# LEOPADMINI.net
KiCad netlist of a schematic drawn in EAGLE
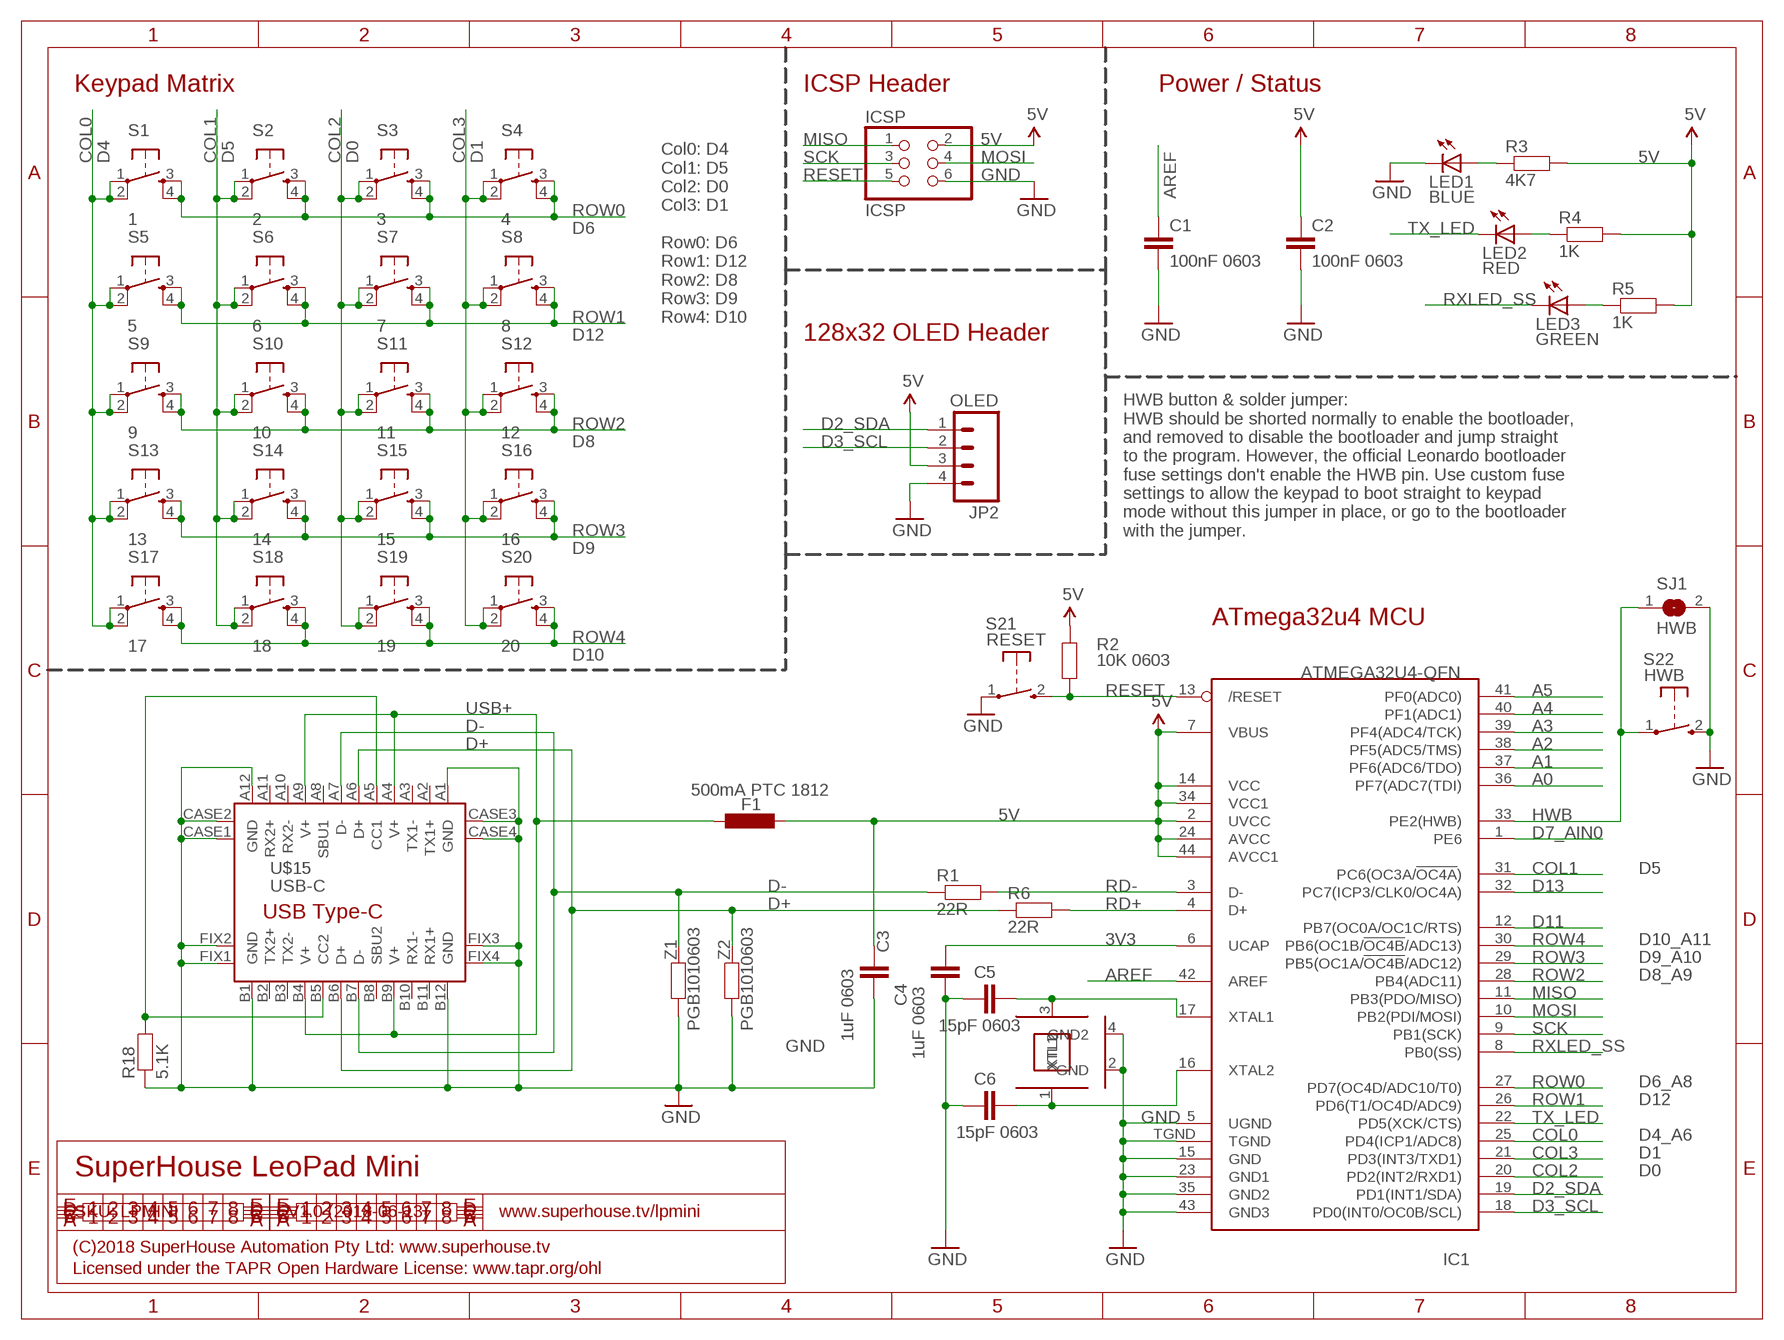
[diagram p0: schematic, sheet 1]

(export (version "E")
  (design (tool "Eeschema 10.0.6"))
  (components
    (comp (ref "C1")
      (value "100nF 0603")
      (footprint "eagle-import:0603")
      (libsource (lib "eagle-import") (part "CAP0603"))
    )
    (comp (ref "C2")
      (value "100nF 0603")
      (footprint "eagle-import:0603")
      (libsource (lib "eagle-import") (part "CAP0603"))
    )
    (comp (ref "C3")
      (value "1uF 0603")
      (footprint "eagle-import:0603")
      (libsource (lib "eagle-import") (part "CAP0603"))
    )
    (comp (ref "C4")
      (value "1uF 0603")
      (footprint "eagle-import:0603")
      (libsource (lib "eagle-import") (part "CAP0603"))
    )
    (comp (ref "C5")
      (value "15pF 0603")
      (footprint "eagle-import:0603")
      (libsource (lib "eagle-import") (part "CAP0603"))
    )
    (comp (ref "C6")
      (value "15pF 0603")
      (footprint "eagle-import:0603")
      (libsource (lib "eagle-import") (part "CAP0603"))
    )
    (comp (ref "F1")
      (value "500mA PTC 1812")
      (footprint "eagle-import:L1812")
      (libsource (lib "eagle-import") (part "L-EUL1812"))
    )
    (comp (ref "IC1")
      (value "ATMEGA32U4-QFN")
      (footprint "eagle-import:QFN-44N")
      (libsource (lib "eagle-import") (part "ATMEGA32U4-QFN"))
    )
    (comp (ref "ICSP")
      (value "ICSP")
      (footprint "eagle-import:2X03")
      (libsource (lib "eagle-import") (part "PINHD-2X3"))
    )
    (comp (ref "JP2")
      (value "OLED")
      (footprint "eagle-import:1X04")
      (libsource (lib "eagle-import") (part "M04PTH"))
    )
    (comp (ref "LED1")
      (value "BLUE")
      (footprint "eagle-import:LED-0603")
      (libsource (lib "eagle-import") (part "LED0603"))
    )
    (comp (ref "LED2")
      (value "RED")
      (footprint "eagle-import:LED-0603")
      (libsource (lib "eagle-import") (part "LED0603"))
    )
    (comp (ref "LED3")
      (value "GREEN")
      (footprint "eagle-import:LED-0603")
      (libsource (lib "eagle-import") (part "LED0603"))
    )
    (comp (ref "R1")
      (value "22R")
      (footprint "eagle-import:0603")
      (libsource (lib "eagle-import") (part "RESISTOR0603"))
    )
    (comp (ref "R2")
      (value "10K 0603")
      (footprint "eagle-import:0603")
      (libsource (lib "eagle-import") (part "freetronics-master-v1.1_RESISTOR0603"))
    )
    (comp (ref "R3")
      (value "4K7")
      (footprint "eagle-import:0603")
      (libsource (lib "eagle-import") (part "RESISTOR0603"))
    )
    (comp (ref "R4")
      (value "1K")
      (footprint "eagle-import:0603")
      (libsource (lib "eagle-import") (part "RESISTOR0603"))
    )
    (comp (ref "R5")
      (value "1K")
      (footprint "eagle-import:0603")
      (libsource (lib "eagle-import") (part "RESISTOR0603"))
    )
    (comp (ref "R6")
      (value "22R")
      (footprint "eagle-import:0603")
      (libsource (lib "eagle-import") (part "RESISTOR0603"))
    )
    (comp (ref "R18")
      (value "5.1K")
      (footprint "eagle-import:0603")
      (libsource (lib "eagle-import") (part "freetronics-original_RESISTOR0603"))
    )
    (comp (ref "S1")
      (value "1")
      (footprint "eagle-import:TACTILE-PTH")
      (libsource (lib "eagle-import") (part "TAC_SWITCHPTH"))
    )
    (comp (ref "S2")
      (value "2")
      (footprint "eagle-import:TACTILE-PTH")
      (libsource (lib "eagle-import") (part "TAC_SWITCHPTH"))
    )
    (comp (ref "S3")
      (value "3")
      (footprint "eagle-import:TACTILE-PTH")
      (libsource (lib "eagle-import") (part "TAC_SWITCHPTH"))
    )
    (comp (ref "S4")
      (value "4")
      (footprint "eagle-import:TACTILE-PTH")
      (libsource (lib "eagle-import") (part "TAC_SWITCHPTH"))
    )
    (comp (ref "S5")
      (value "5")
      (footprint "eagle-import:TACTILE-PTH")
      (libsource (lib "eagle-import") (part "TAC_SWITCHPTH"))
    )
    (comp (ref "S6")
      (value "6")
      (footprint "eagle-import:TACTILE-PTH")
      (libsource (lib "eagle-import") (part "TAC_SWITCHPTH"))
    )
    (comp (ref "S7")
      (value "7")
      (footprint "eagle-import:TACTILE-PTH")
      (libsource (lib "eagle-import") (part "TAC_SWITCHPTH"))
    )
    (comp (ref "S8")
      (value "8")
      (footprint "eagle-import:TACTILE-PTH")
      (libsource (lib "eagle-import") (part "TAC_SWITCHPTH"))
    )
    (comp (ref "S9")
      (value "9")
      (footprint "eagle-import:TACTILE-PTH")
      (libsource (lib "eagle-import") (part "TAC_SWITCHPTH"))
    )
    (comp (ref "S10")
      (value "10")
      (footprint "eagle-import:TACTILE-PTH")
      (libsource (lib "eagle-import") (part "TAC_SWITCHPTH"))
    )
    (comp (ref "S11")
      (value "11")
      (footprint "eagle-import:TACTILE-PTH")
      (libsource (lib "eagle-import") (part "TAC_SWITCHPTH"))
    )
    (comp (ref "S12")
      (value "12")
      (footprint "eagle-import:TACTILE-PTH")
      (libsource (lib "eagle-import") (part "TAC_SWITCHPTH"))
    )
    (comp (ref "S13")
      (value "13")
      (footprint "eagle-import:TACTILE-PTH")
      (libsource (lib "eagle-import") (part "TAC_SWITCHPTH"))
    )
    (comp (ref "S14")
      (value "14")
      (footprint "eagle-import:TACTILE-PTH")
      (libsource (lib "eagle-import") (part "TAC_SWITCHPTH"))
    )
    (comp (ref "S15")
      (value "15")
      (footprint "eagle-import:TACTILE-PTH")
      (libsource (lib "eagle-import") (part "TAC_SWITCHPTH"))
    )
    (comp (ref "S16")
      (value "16")
      (footprint "eagle-import:TACTILE-PTH")
      (libsource (lib "eagle-import") (part "TAC_SWITCHPTH"))
    )
    (comp (ref "S17")
      (value "17")
      (footprint "eagle-import:TACTILE-PTH")
      (libsource (lib "eagle-import") (part "TAC_SWITCHPTH"))
    )
    (comp (ref "S18")
      (value "18")
      (footprint "eagle-import:TACTILE-PTH")
      (libsource (lib "eagle-import") (part "TAC_SWITCHPTH"))
    )
    (comp (ref "S19")
      (value "19")
      (footprint "eagle-import:TACTILE-PTH")
      (libsource (lib "eagle-import") (part "TAC_SWITCHPTH"))
    )
    (comp (ref "S20")
      (value "20")
      (footprint "eagle-import:TACTILE-PTH")
      (libsource (lib "eagle-import") (part "TAC_SWITCHPTH"))
    )
    (comp (ref "S21")
      (value "RESET")
      (footprint "eagle-import:TACTILE_SWITCH_SMD_2PIN_TINY")
      (libsource (lib "eagle-import") (part "TAC_SWITCH_2PINSMT"))
    )
    (comp (ref "S22")
      (value "HWB")
      (footprint "eagle-import:TACTILE_SWITCH_SMD_2PIN_TINY")
      (libsource (lib "eagle-import") (part "TAC_SWITCH_2PINSMT"))
    )
    (comp (ref "SJ1")
      (value "HWB")
      (footprint "eagle-import:SJ")
      (libsource (lib "eagle-import") (part "SJN"))
    )
    (comp (ref "U$15")
      (value "USB-C")
      (footprint "eagle-import:USB-C-U52A")
      (libsource (lib "eagle-import") (part "USB-C"))
    )
    (comp (ref "XTL1")
      (value "16MHz")
      (footprint "eagle-import:CRYSTAL-SMD-3X2")
      (libsource (lib "eagle-import") (part "CRYSTAL-GND3X2"))
    )
    (comp (ref "Z1")
      (value "PGB1010603")
      (footprint "eagle-import:0603")
      (libsource (lib "eagle-import") (part "freetronics-master-v1.1_RESISTOR0603"))
    )
    (comp (ref "Z2")
      (value "PGB1010603")
      (footprint "eagle-import:0603")
      (libsource (lib "eagle-import") (part "freetronics-master-v1.1_RESISTOR0603"))
    )
  )
  (nets
    (net (code "1") (name "/3V3") (class "Default")
      (node (ref "C4") (pin "2") (pinfunction "2_2") (pintype "passive"))
      (node (ref "IC1") (pin "6") (pinfunction "UCAP_6") (pintype "bidirectional"))
    )
    (net (code "2") (name "/A0") (class "Default")
      (node (ref "IC1") (pin "36") (pinfunction "PF7(ADC7(TDI)_36") (pintype "bidirectional"))
    )
    (net (code "3") (name "/A1") (class "Default")
      (node (ref "IC1") (pin "37") (pinfunction "PF6(ADC6/TDO)_37") (pintype "bidirectional"))
    )
    (net (code "4") (name "/A2") (class "Default")
      (node (ref "IC1") (pin "38") (pinfunction "PF5(ADC5/TMS)_38") (pintype "bidirectional"))
    )
    (net (code "5") (name "/A3") (class "Default")
      (node (ref "IC1") (pin "39") (pinfunction "PF4(ADC4/TCK)_39") (pintype "bidirectional"))
    )
    (net (code "6") (name "/A4") (class "Default")
      (node (ref "IC1") (pin "40") (pinfunction "PF1(ADC1)_40") (pintype "bidirectional"))
    )
    (net (code "7") (name "/A5") (class "Default")
      (node (ref "IC1") (pin "41") (pinfunction "PF0(ADC0)_41") (pintype "bidirectional"))
    )
    (net (code "8") (name "/AREF") (class "Default")
      (node (ref "C1") (pin "1") (pinfunction "1_1") (pintype "passive"))
      (node (ref "IC1") (pin "42") (pinfunction "AREF_42") (pintype "bidirectional"))
    )
    (net (code "9") (name "/COL0") (class "Default")
      (node (ref "IC1") (pin "25") (pinfunction "PD4(ICP1/ADC8)_25") (pintype "bidirectional"))
      (node (ref "S1") (pin "1") (pinfunction "1_1") (pintype "passive"))
      (node (ref "S1") (pin "2") (pinfunction "2_2") (pintype "passive"))
      (node (ref "S13") (pin "1") (pinfunction "1_1") (pintype "passive"))
      (node (ref "S13") (pin "2") (pinfunction "2_2") (pintype "passive"))
      (node (ref "S17") (pin "1") (pinfunction "1_1") (pintype "passive"))
      (node (ref "S17") (pin "2") (pinfunction "2_2") (pintype "passive"))
      (node (ref "S5") (pin "1") (pinfunction "1_1") (pintype "passive"))
      (node (ref "S5") (pin "2") (pinfunction "2_2") (pintype "passive"))
      (node (ref "S9") (pin "1") (pinfunction "1_1") (pintype "passive"))
      (node (ref "S9") (pin "2") (pinfunction "2_2") (pintype "passive"))
    )
    (net (code "10") (name "/COL1") (class "Default")
      (node (ref "IC1") (pin "31") (pinfunction "PC6(OC3A/~{OC4A})_31") (pintype "bidirectional"))
      (node (ref "S10") (pin "1") (pinfunction "1_1") (pintype "passive"))
      (node (ref "S10") (pin "2") (pinfunction "2_2") (pintype "passive"))
      (node (ref "S14") (pin "1") (pinfunction "1_1") (pintype "passive"))
      (node (ref "S14") (pin "2") (pinfunction "2_2") (pintype "passive"))
      (node (ref "S18") (pin "1") (pinfunction "1_1") (pintype "passive"))
      (node (ref "S18") (pin "2") (pinfunction "2_2") (pintype "passive"))
      (node (ref "S2") (pin "1") (pinfunction "1_1") (pintype "passive"))
      (node (ref "S2") (pin "2") (pinfunction "2_2") (pintype "passive"))
      (node (ref "S6") (pin "1") (pinfunction "1_1") (pintype "passive"))
      (node (ref "S6") (pin "2") (pinfunction "2_2") (pintype "passive"))
    )
    (net (code "11") (name "/COL2") (class "Default")
      (node (ref "IC1") (pin "20") (pinfunction "PD2(INT2/RXD1)_20") (pintype "bidirectional"))
      (node (ref "S11") (pin "1") (pinfunction "1_1") (pintype "passive"))
      (node (ref "S11") (pin "2") (pinfunction "2_2") (pintype "passive"))
      (node (ref "S15") (pin "1") (pinfunction "1_1") (pintype "passive"))
      (node (ref "S15") (pin "2") (pinfunction "2_2") (pintype "passive"))
      (node (ref "S19") (pin "1") (pinfunction "1_1") (pintype "passive"))
      (node (ref "S19") (pin "2") (pinfunction "2_2") (pintype "passive"))
      (node (ref "S3") (pin "1") (pinfunction "1_1") (pintype "passive"))
      (node (ref "S3") (pin "2") (pinfunction "2_2") (pintype "passive"))
      (node (ref "S7") (pin "1") (pinfunction "1_1") (pintype "passive"))
      (node (ref "S7") (pin "2") (pinfunction "2_2") (pintype "passive"))
    )
    (net (code "12") (name "/COL3") (class "Default")
      (node (ref "IC1") (pin "21") (pinfunction "PD3(INT3/TXD1)_21") (pintype "bidirectional"))
      (node (ref "S12") (pin "1") (pinfunction "1_1") (pintype "passive"))
      (node (ref "S12") (pin "2") (pinfunction "2_2") (pintype "passive"))
      (node (ref "S16") (pin "1") (pinfunction "1_1") (pintype "passive"))
      (node (ref "S16") (pin "2") (pinfunction "2_2") (pintype "passive"))
      (node (ref "S20") (pin "1") (pinfunction "1_1") (pintype "passive"))
      (node (ref "S20") (pin "2") (pinfunction "2_2") (pintype "passive"))
      (node (ref "S4") (pin "1") (pinfunction "1_1") (pintype "passive"))
      (node (ref "S4") (pin "2") (pinfunction "2_2") (pintype "passive"))
      (node (ref "S8") (pin "1") (pinfunction "1_1") (pintype "passive"))
      (node (ref "S8") (pin "2") (pinfunction "2_2") (pintype "passive"))
    )
    (net (code "13") (name "/D+") (class "Default")
      (node (ref "R6") (pin "1") (pinfunction "1_1") (pintype "passive"))
      (node (ref "U$15") (pin "A6") (pinfunction "D+_A6") (pintype "bidirectional"))
      (node (ref "U$15") (pin "B6") (pinfunction "D+_B6") (pintype "bidirectional"))
      (node (ref "Z2") (pin "2") (pinfunction "2_2") (pintype "passive"))
    )
    (net (code "14") (name "/D-") (class "Default")
      (node (ref "R1") (pin "1") (pinfunction "1_1") (pintype "passive"))
      (node (ref "U$15") (pin "A7") (pinfunction "D-_A7") (pintype "bidirectional"))
      (node (ref "U$15") (pin "B7") (pinfunction "D-_B7") (pintype "bidirectional"))
      (node (ref "Z1") (pin "2") (pinfunction "2_2") (pintype "passive"))
    )
    (net (code "15") (name "/D2_SDA") (class "Default")
      (node (ref "IC1") (pin "19") (pinfunction "PD1(INT1/SDA)_19") (pintype "bidirectional"))
      (node (ref "JP2") (pin "1") (pinfunction "1_1") (pintype "passive"))
    )
    (net (code "16") (name "/D3_SCL") (class "Default")
      (node (ref "IC1") (pin "18") (pinfunction "PD0(INT0/OC0B/SCL)_18") (pintype "bidirectional"))
      (node (ref "JP2") (pin "2") (pinfunction "2_2") (pintype "passive"))
    )
    (net (code "17") (name "/D7_AIN0") (class "Default")
      (node (ref "IC1") (pin "1") (pinfunction "PE6_1") (pintype "bidirectional"))
    )
    (net (code "18") (name "/D11") (class "Default")
      (node (ref "IC1") (pin "12") (pinfunction "PB7(OC0A/OC1C/RTS)_12") (pintype "bidirectional"))
    )
    (net (code "19") (name "/D13") (class "Default")
      (node (ref "IC1") (pin "32") (pinfunction "PC7(ICP3/CLK0/OC4A)_32") (pintype "bidirectional"))
    )
    (net (code "20") (name "/HWB") (class "Default")
      (node (ref "IC1") (pin "33") (pinfunction "PE2(HWB)_33") (pintype "bidirectional"))
      (node (ref "S22") (pin "1") (pinfunction "P_1") (pintype "passive"))
      (node (ref "SJ1") (pin "1") (pinfunction "1_1") (pintype "passive"))
    )
    (net (code "21") (name "/MISO") (class "Default")
      (node (ref "IC1") (pin "11") (pinfunction "PB3(PDO/MISO)_11") (pintype "bidirectional"))
      (node (ref "ICSP") (pin "1") (pinfunction "1_1") (pintype "passive"))
    )
    (net (code "22") (name "/MOSI") (class "Default")
      (node (ref "IC1") (pin "10") (pinfunction "PB2(PDI/MOSI)_10") (pintype "bidirectional"))
      (node (ref "ICSP") (pin "4") (pinfunction "4_4") (pintype "passive"))
    )
    (net (code "23") (name "/RD+") (class "Default")
      (node (ref "IC1") (pin "4") (pinfunction "D+_4") (pintype "bidirectional"))
      (node (ref "R6") (pin "2") (pinfunction "2_2") (pintype "passive"))
    )
    (net (code "24") (name "/RD-") (class "Default")
      (node (ref "IC1") (pin "3") (pinfunction "D-_3") (pintype "bidirectional"))
      (node (ref "R1") (pin "2") (pinfunction "2_2") (pintype "passive"))
    )
    (net (code "25") (name "/RESET") (class "Default")
      (node (ref "IC1") (pin "13") (pinfunction "/RESET_13") (pintype "bidirectional"))
      (node (ref "ICSP") (pin "5") (pinfunction "5_5") (pintype "passive"))
      (node (ref "R2") (pin "1") (pinfunction "1_1") (pintype "passive"))
      (node (ref "S21") (pin "2") (pinfunction "S_2") (pintype "passive"))
    )
    (net (code "26") (name "/ROW0") (class "Default")
      (node (ref "IC1") (pin "27") (pinfunction "PD7(OC4D/ADC10/T0)_27") (pintype "bidirectional"))
      (node (ref "S1") (pin "3") (pinfunction "3_3") (pintype "passive"))
      (node (ref "S1") (pin "4") (pinfunction "4_4") (pintype "passive"))
      (node (ref "S2") (pin "3") (pinfunction "3_3") (pintype "passive"))
      (node (ref "S2") (pin "4") (pinfunction "4_4") (pintype "passive"))
      (node (ref "S3") (pin "3") (pinfunction "3_3") (pintype "passive"))
      (node (ref "S3") (pin "4") (pinfunction "4_4") (pintype "passive"))
      (node (ref "S4") (pin "3") (pinfunction "3_3") (pintype "passive"))
      (node (ref "S4") (pin "4") (pinfunction "4_4") (pintype "passive"))
    )
    (net (code "27") (name "/ROW1") (class "Default")
      (node (ref "IC1") (pin "26") (pinfunction "PD6(T1/OC4D/ADC9)_26") (pintype "bidirectional"))
      (node (ref "S5") (pin "3") (pinfunction "3_3") (pintype "passive"))
      (node (ref "S5") (pin "4") (pinfunction "4_4") (pintype "passive"))
      (node (ref "S6") (pin "3") (pinfunction "3_3") (pintype "passive"))
      (node (ref "S6") (pin "4") (pinfunction "4_4") (pintype "passive"))
      (node (ref "S7") (pin "3") (pinfunction "3_3") (pintype "passive"))
      (node (ref "S7") (pin "4") (pinfunction "4_4") (pintype "passive"))
      (node (ref "S8") (pin "3") (pinfunction "3_3") (pintype "passive"))
      (node (ref "S8") (pin "4") (pinfunction "4_4") (pintype "passive"))
    )
    (net (code "28") (name "/ROW2") (class "Default")
      (node (ref "IC1") (pin "28") (pinfunction "PB4(ADC11)_28") (pintype "bidirectional"))
      (node (ref "S10") (pin "3") (pinfunction "3_3") (pintype "passive"))
      (node (ref "S10") (pin "4") (pinfunction "4_4") (pintype "passive"))
      (node (ref "S11") (pin "3") (pinfunction "3_3") (pintype "passive"))
      (node (ref "S11") (pin "4") (pinfunction "4_4") (pintype "passive"))
      (node (ref "S12") (pin "3") (pinfunction "3_3") (pintype "passive"))
      (node (ref "S12") (pin "4") (pinfunction "4_4") (pintype "passive"))
      (node (ref "S9") (pin "3") (pinfunction "3_3") (pintype "passive"))
      (node (ref "S9") (pin "4") (pinfunction "4_4") (pintype "passive"))
    )
    (net (code "29") (name "/ROW3") (class "Default")
      (node (ref "IC1") (pin "29") (pinfunction "PB5(OC1A/~{OC4B}/ADC12)_29") (pintype "bidirectional"))
      (node (ref "S13") (pin "3") (pinfunction "3_3") (pintype "passive"))
      (node (ref "S13") (pin "4") (pinfunction "4_4") (pintype "passive"))
      (node (ref "S14") (pin "3") (pinfunction "3_3") (pintype "passive"))
      (node (ref "S14") (pin "4") (pinfunction "4_4") (pintype "passive"))
      (node (ref "S15") (pin "3") (pinfunction "3_3") (pintype "passive"))
      (node (ref "S15") (pin "4") (pinfunction "4_4") (pintype "passive"))
      (node (ref "S16") (pin "3") (pinfunction "3_3") (pintype "passive"))
      (node (ref "S16") (pin "4") (pinfunction "4_4") (pintype "passive"))
    )
    (net (code "30") (name "/ROW4") (class "Default")
      (node (ref "IC1") (pin "30") (pinfunction "PB6(OC1B/~{OC4B}/ADC13)_30") (pintype "bidirectional"))
      (node (ref "S17") (pin "3") (pinfunction "3_3") (pintype "passive"))
      (node (ref "S17") (pin "4") (pinfunction "4_4") (pintype "passive"))
      (node (ref "S18") (pin "3") (pinfunction "3_3") (pintype "passive"))
      (node (ref "S18") (pin "4") (pinfunction "4_4") (pintype "passive"))
      (node (ref "S19") (pin "3") (pinfunction "3_3") (pintype "passive"))
      (node (ref "S19") (pin "4") (pinfunction "4_4") (pintype "passive"))
      (node (ref "S20") (pin "3") (pinfunction "3_3") (pintype "passive"))
      (node (ref "S20") (pin "4") (pinfunction "4_4") (pintype "passive"))
    )
    (net (code "31") (name "/RXLED_SS") (class "Default")
      (node (ref "IC1") (pin "8") (pinfunction "PB0(SS)_8") (pintype "bidirectional"))
      (node (ref "LED3") (pin "C") (pinfunction "C_C") (pintype "passive"))
    )
    (net (code "32") (name "/SCK") (class "Default")
      (node (ref "IC1") (pin "9") (pinfunction "PB1(SCK)_9") (pintype "bidirectional"))
      (node (ref "ICSP") (pin "3") (pinfunction "3_3") (pintype "passive"))
    )
    (net (code "33") (name "/TX_LED") (class "Default")
      (node (ref "IC1") (pin "22") (pinfunction "PD5(XCK/CTS)_22") (pintype "bidirectional"))
      (node (ref "LED2") (pin "C") (pinfunction "C_C") (pintype "passive"))
    )
    (net (code "34") (name "/USB+") (class "Default")
      (node (ref "F1") (pin "1") (pinfunction "1_1") (pintype "passive"))
      (node (ref "U$15") (pin "A4") (pinfunction "V+_A4") (pintype "power_in"))
      (node (ref "U$15") (pin "A9") (pinfunction "V+_A9") (pintype "power_in"))
      (node (ref "U$15") (pin "B4") (pinfunction "V+_B4") (pintype "power_in"))
      (node (ref "U$15") (pin "B9") (pinfunction "V+_B9") (pintype "power_in"))
    )
    (net (code "35") (name "5V") (class "Default")
      (node (ref "C2") (pin "1") (pinfunction "1_1") (pintype "passive"))
      (node (ref "C3") (pin "1") (pinfunction "1_1") (pintype "passive"))
      (node (ref "F1") (pin "2") (pinfunction "2_2") (pintype "passive"))
      (node (ref "IC1") (pin "14") (pinfunction "VCC_14") (pintype "bidirectional"))
      (node (ref "IC1") (pin "2") (pinfunction "UVCC_2") (pintype "bidirectional"))
      (node (ref "IC1") (pin "24") (pinfunction "AVCC_24") (pintype "bidirectional"))
      (node (ref "IC1") (pin "34") (pinfunction "VCC1_34") (pintype "bidirectional"))
      (node (ref "IC1") (pin "44") (pinfunction "AVCC1_44") (pintype "bidirectional"))
      (node (ref "IC1") (pin "7") (pinfunction "VBUS_7") (pintype "bidirectional"))
      (node (ref "ICSP") (pin "2") (pinfunction "2_2") (pintype "passive"))
      (node (ref "JP2") (pin "3") (pinfunction "3_3") (pintype "passive"))
      (node (ref "R2") (pin "2") (pinfunction "2_2") (pintype "passive"))
      (node (ref "R3") (pin "2") (pinfunction "2_2") (pintype "passive"))
      (node (ref "R4") (pin "2") (pinfunction "2_2") (pintype "passive"))
      (node (ref "R5") (pin "2") (pinfunction "2_2") (pintype "passive"))
    )
    (net (code "36") (name "GND") (class "Default")
      (node (ref "C1") (pin "2") (pinfunction "2_2") (pintype "passive"))
      (node (ref "C2") (pin "2") (pinfunction "2_2") (pintype "passive"))
      (node (ref "C3") (pin "2") (pinfunction "2_2") (pintype "passive"))
      (node (ref "C4") (pin "1") (pinfunction "1_1") (pintype "passive"))
      (node (ref "C5") (pin "1") (pinfunction "1_1") (pintype "passive"))
      (node (ref "C6") (pin "1") (pinfunction "1_1") (pintype "passive"))
      (node (ref "IC1") (pin "15") (pinfunction "GND_15") (pintype "bidirectional"))
      (node (ref "IC1") (pin "23") (pinfunction "GND1_23") (pintype "bidirectional"))
      (node (ref "IC1") (pin "35") (pinfunction "GND2_35") (pintype "bidirectional"))
      (node (ref "IC1") (pin "43") (pinfunction "GND3_43") (pintype "bidirectional"))
      (node (ref "IC1") (pin "5") (pinfunction "UGND_5") (pintype "bidirectional"))
      (node (ref "IC1") (pin "TGND") (pinfunction "TGND_TGND") (pintype "bidirectional"))
      (node (ref "ICSP") (pin "6") (pinfunction "6_6") (pintype "passive"))
      (node (ref "JP2") (pin "4") (pinfunction "4_4") (pintype "passive"))
      (node (ref "LED1") (pin "C") (pinfunction "C_C") (pintype "passive"))
      (node (ref "R18") (pin "1") (pinfunction "1_1") (pintype "passive"))
      (node (ref "S21") (pin "1") (pinfunction "P_1") (pintype "passive"))
      (node (ref "S22") (pin "2") (pinfunction "S_2") (pintype "passive"))
      (node (ref "SJ1") (pin "2") (pinfunction "2_2") (pintype "passive"))
      (node (ref "U$15") (pin "A1") (pinfunction "GND_A1") (pintype "power_in"))
      (node (ref "U$15") (pin "A12") (pinfunction "GND_A12") (pintype "power_in"))
      (node (ref "U$15") (pin "B1") (pinfunction "GND_B1") (pintype "power_in"))
      (node (ref "U$15") (pin "B12") (pinfunction "GND_B12") (pintype "power_in"))
      (node (ref "U$15") (pin "CASE1") (pinfunction "GND_CASE1") (pintype "power_in"))
      (node (ref "U$15") (pin "CASE2") (pinfunction "GND_CASE2") (pintype "power_in"))
      (node (ref "U$15") (pin "CASE3") (pinfunction "GND_CASE3") (pintype "power_in"))
      (node (ref "U$15") (pin "CASE4") (pinfunction "GND_CASE4") (pintype "power_in"))
      (node (ref "U$15") (pin "FIX1") (pinfunction "GND_FIX1") (pintype "power_in"))
      (node (ref "U$15") (pin "FIX2") (pinfunction "GND_FIX2") (pintype "power_in"))
      (node (ref "U$15") (pin "FIX3") (pinfunction "GND_FIX3") (pintype "power_in"))
      (node (ref "U$15") (pin "FIX4") (pinfunction "GND_FIX4") (pintype "power_in"))
      (node (ref "XTL1") (pin "2") (pinfunction "GND_2") (pintype "bidirectional"))
      (node (ref "XTL1") (pin "4") (pinfunction "GND2_4") (pintype "bidirectional"))
      (node (ref "Z1") (pin "1") (pinfunction "1_1") (pintype "passive"))
      (node (ref "Z2") (pin "1") (pinfunction "1_1") (pintype "passive"))
    )
    (net (code "37") (name "Net-(IC1-XTAL1)") (class "Default")
      (node (ref "C5") (pin "2") (pinfunction "2_2") (pintype "passive"))
      (node (ref "IC1") (pin "17") (pinfunction "XTAL1_17") (pintype "bidirectional"))
      (node (ref "XTL1") (pin "3") (pinfunction "XTL2_3") (pintype "bidirectional"))
    )
    (net (code "38") (name "Net-(IC1-XTAL2)") (class "Default")
      (node (ref "C6") (pin "2") (pinfunction "2_2") (pintype "passive"))
      (node (ref "IC1") (pin "16") (pinfunction "XTAL2_16") (pintype "bidirectional"))
      (node (ref "XTL1") (pin "1") (pinfunction "XTL1_1") (pintype "bidirectional"))
    )
    (net (code "39") (name "Net-(LED1-PadA)") (class "Default")
      (node (ref "LED1") (pin "A") (pinfunction "A_A") (pintype "passive"))
      (node (ref "R3") (pin "1") (pinfunction "1_1") (pintype "passive"))
    )
    (net (code "40") (name "Net-(LED2-PadA)") (class "Default")
      (node (ref "LED2") (pin "A") (pinfunction "A_A") (pintype "passive"))
      (node (ref "R4") (pin "1") (pinfunction "1_1") (pintype "passive"))
    )
    (net (code "41") (name "Net-(LED3-PadA)") (class "Default")
      (node (ref "LED3") (pin "A") (pinfunction "A_A") (pintype "passive"))
      (node (ref "R5") (pin "1") (pinfunction "1_1") (pintype "passive"))
    )
    (net (code "42") (name "Net-(U$15-CC1)") (class "Default")
      (node (ref "R18") (pin "2") (pinfunction "2_2") (pintype "passive"))
      (node (ref "U$15") (pin "A5") (pinfunction "CC1_A5") (pintype "bidirectional"))
      (node (ref "U$15") (pin "B5") (pinfunction "CC2_B5") (pintype "bidirectional"))
    )
    (net (code "43") (name "unconnected-(U$15-RX1+-PadB11)") (class "Default")
      (node (ref "U$15") (pin "B11") (pinfunction "RX1+_B11") (pintype "bidirectional"))
    )
    (net (code "44") (name "unconnected-(U$15-RX1--PadB10)") (class "Default")
      (node (ref "U$15") (pin "B10") (pinfunction "RX1-_B10") (pintype "bidirectional"))
    )
    (net (code "45") (name "unconnected-(U$15-RX2+-PadA11)") (class "Default")
      (node (ref "U$15") (pin "A11") (pinfunction "RX2+_A11") (pintype "bidirectional"))
    )
    (net (code "46") (name "unconnected-(U$15-RX2--PadA10)") (class "Default")
      (node (ref "U$15") (pin "A10") (pinfunction "RX2-_A10") (pintype "bidirectional"))
    )
    (net (code "47") (name "unconnected-(U$15-SBU1-PadA8)") (class "Default")
      (node (ref "U$15") (pin "A8") (pinfunction "SBU1_A8") (pintype "bidirectional"))
    )
    (net (code "48") (name "unconnected-(U$15-SBU2-PadB8)") (class "Default")
      (node (ref "U$15") (pin "B8") (pinfunction "SBU2_B8") (pintype "bidirectional"))
    )
    (net (code "49") (name "unconnected-(U$15-TX1+-PadA2)") (class "Default")
      (node (ref "U$15") (pin "A2") (pinfunction "TX1+_A2") (pintype "bidirectional"))
    )
    (net (code "50") (name "unconnected-(U$15-TX1--PadA3)") (class "Default")
      (node (ref "U$15") (pin "A3") (pinfunction "TX1-_A3") (pintype "bidirectional"))
    )
    (net (code "51") (name "unconnected-(U$15-TX2+-PadB2)") (class "Default")
      (node (ref "U$15") (pin "B2") (pinfunction "TX2+_B2") (pintype "bidirectional"))
    )
    (net (code "52") (name "unconnected-(U$15-TX2--PadB3)") (class "Default")
      (node (ref "U$15") (pin "B3") (pinfunction "TX2-_B3") (pintype "bidirectional"))
    )
  )
)
